# Board_Layout.net
KiCad netlist of a schematic drawn in EAGLE
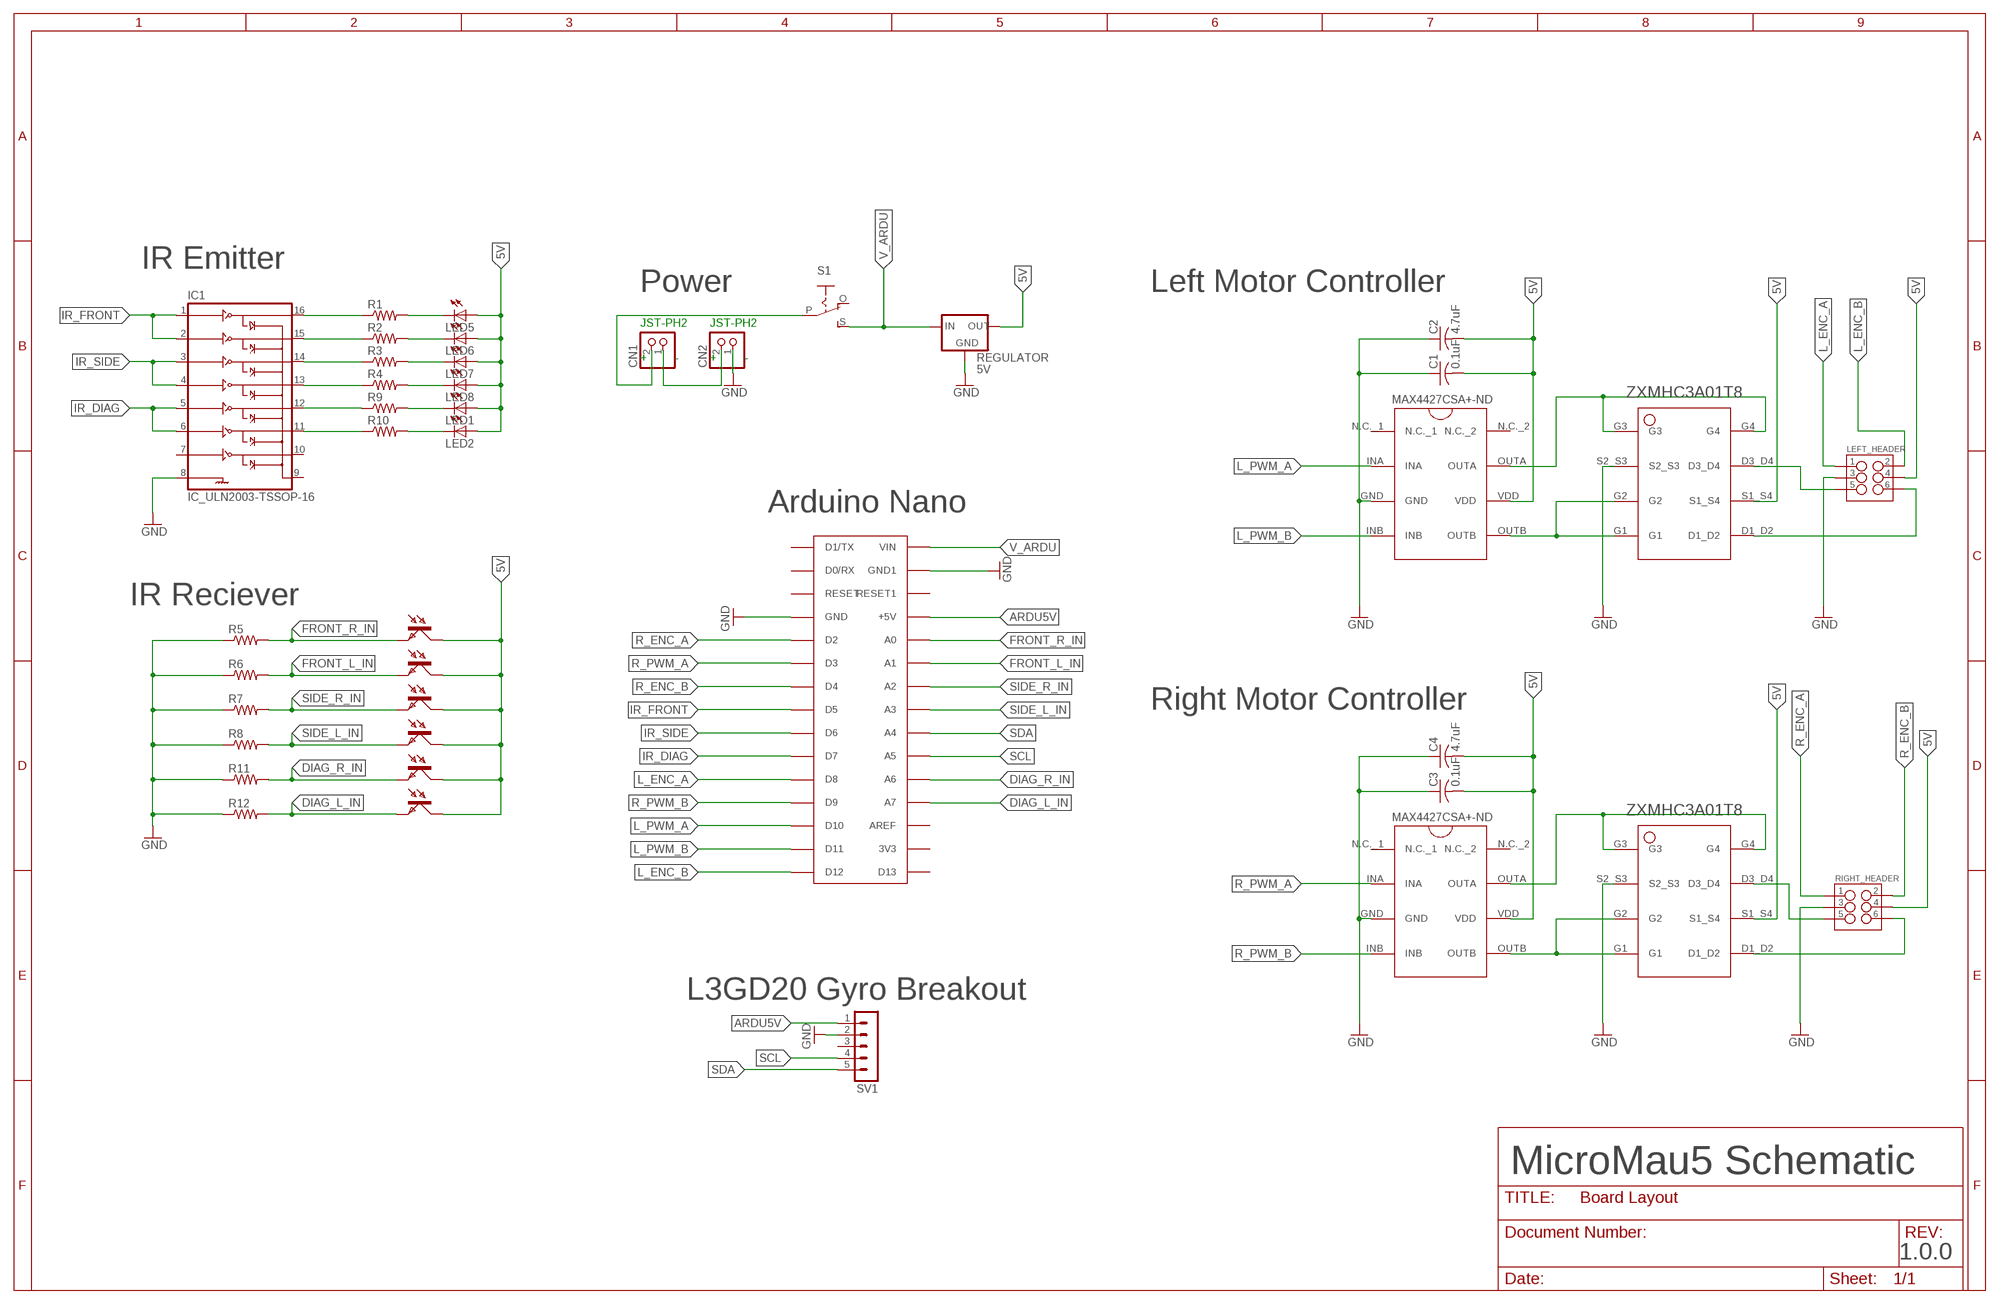
[diagram p0: schematic, sheet 1]

(export (version "E")
  (design (tool "Eeschema 10.0.6"))
  (components
    (comp (ref "C1")
      (value "0.1uF")
      (footprint "eagle-import:C0805")
      (libsource (lib "eagle-import") (part "C-USC0805"))
    )
    (comp (ref "C2")
      (value "4.7uF")
      (footprint "eagle-import:C0805")
      (libsource (lib "eagle-import") (part "C-USC0805"))
    )
    (comp (ref "C3")
      (value "0.1uF")
      (footprint "eagle-import:C0805")
      (libsource (lib "eagle-import") (part "C-USC0805"))
    )
    (comp (ref "C4")
      (value "4.7uF")
      (footprint "eagle-import:C0805")
      (libsource (lib "eagle-import") (part "C-USC0805"))
    )
    (comp (ref "CN1")
      (value "JST_2PIN-THM")
      (footprint "eagle-import:JST-PH-2-THM")
      (libsource (lib "eagle-import") (part "JST_2PIN-THM"))
    )
    (comp (ref "CN2")
      (value "JST_2PIN-THM")
      (footprint "eagle-import:JST-PH-2-THM")
      (libsource (lib "eagle-import") (part "JST_2PIN-THM"))
    )
    (comp (ref "IC1")
      (value "IC_ULN2003-TSSOP-16")
      (footprint "eagle-import:TSSOP-16")
      (libsource (lib "eagle-import") (part "IC_ULN2003-TSSOP-16"))
    )
    (comp (ref "LED1")
      (value "LED5MM")
      (footprint "eagle-import:LED5MM")
      (libsource (lib "eagle-import") (part "LED5MM"))
    )
    (comp (ref "LED2")
      (value "LED5MM")
      (footprint "eagle-import:LED5MM")
      (libsource (lib "eagle-import") (part "LED5MM"))
    )
    (comp (ref "LED5")
      (value "LED5MM")
      (footprint "eagle-import:LED5MM")
      (libsource (lib "eagle-import") (part "LED5MM"))
    )
    (comp (ref "LED6")
      (value "LED5MM")
      (footprint "eagle-import:LED5MM")
      (libsource (lib "eagle-import") (part "LED5MM"))
    )
    (comp (ref "LED7")
      (value "LED5MM")
      (footprint "eagle-import:LED5MM")
      (libsource (lib "eagle-import") (part "LED5MM"))
    )
    (comp (ref "LED8")
      (value "LED5MM")
      (footprint "eagle-import:LED5MM")
      (libsource (lib "eagle-import") (part "LED5MM"))
    )
    (comp (ref "LEFT_HEADER")
      (value "M03X2SHROUD")
      (footprint "eagle-import:2X3-SHROUDED")
      (libsource (lib "eagle-import") (part "M03X2SHROUD"))
    )
    (comp (ref "R1")
      (value "R-US_M0805")
      (footprint "eagle-import:M0805")
      (libsource (lib "eagle-import") (part "R-US_M0805"))
    )
    (comp (ref "R2")
      (value "R-US_M0805")
      (footprint "eagle-import:M0805")
      (libsource (lib "eagle-import") (part "R-US_M0805"))
    )
    (comp (ref "R3")
      (value "R-US_M0805")
      (footprint "eagle-import:M0805")
      (libsource (lib "eagle-import") (part "R-US_M0805"))
    )
    (comp (ref "R4")
      (value "R-US_M0805")
      (footprint "eagle-import:M0805")
      (libsource (lib "eagle-import") (part "R-US_M0805"))
    )
    (comp (ref "R5")
      (value "R-US_R0805")
      (footprint "eagle-import:R0805")
      (libsource (lib "eagle-import") (part "R-US_R0805"))
    )
    (comp (ref "R6")
      (value "R-US_R0805")
      (footprint "eagle-import:R0805")
      (libsource (lib "eagle-import") (part "R-US_R0805"))
    )
    (comp (ref "R7")
      (value "R-US_R0805")
      (footprint "eagle-import:R0805")
      (libsource (lib "eagle-import") (part "R-US_R0805"))
    )
    (comp (ref "R8")
      (value "R-US_R0805")
      (footprint "eagle-import:R0805")
      (libsource (lib "eagle-import") (part "R-US_R0805"))
    )
    (comp (ref "R9")
      (value "R-US_M0805")
      (footprint "eagle-import:M0805")
      (libsource (lib "eagle-import") (part "R-US_M0805"))
    )
    (comp (ref "R10")
      (value "R-US_M0805")
      (footprint "eagle-import:M0805")
      (libsource (lib "eagle-import") (part "R-US_M0805"))
    )
    (comp (ref "R11")
      (value "R-US_R0805")
      (footprint "eagle-import:R0805")
      (libsource (lib "eagle-import") (part "R-US_R0805"))
    )
    (comp (ref "R12")
      (value "R-US_R0805")
      (footprint "eagle-import:R0805")
      (libsource (lib "eagle-import") (part "R-US_R0805"))
    )
    (comp (ref "REGULATOR")
      (value "5V")
      (footprint "eagle-import:TO92-INLINE")
      (libsource (lib "eagle-import") (part "MCP1700INLINE"))
    )
    (comp (ref "RIGHT_HEADER")
      (value "M03X2SHROUD")
      (footprint "eagle-import:2X3-SHROUDED")
      (libsource (lib "eagle-import") (part "M03X2SHROUD"))
    )
    (comp (ref "S1")
      (value "EG1218S")
      (footprint "eagle-import:EG1218")
      (libsource (lib "eagle-import") (part "EG1218S"))
    )
    (comp (ref "SV1")
      (value "MA05-1")
      (footprint "eagle-import:MA05-1")
      (libsource (lib "eagle-import") (part "MA05-1"))
    )
    (comp (ref "T1")
      (value "BPX81")
      (footprint "eagle-import:BPX81")
      (libsource (lib "eagle-import") (part "BPX81"))
    )
    (comp (ref "T2")
      (value "BPX81")
      (footprint "eagle-import:BPX81")
      (libsource (lib "eagle-import") (part "BPX81"))
    )
    (comp (ref "T3")
      (value "BPX81")
      (footprint "eagle-import:BPX81")
      (libsource (lib "eagle-import") (part "BPX81"))
    )
    (comp (ref "T4")
      (value "BPX81")
      (footprint "eagle-import:BPX81")
      (libsource (lib "eagle-import") (part "BPX81"))
    )
    (comp (ref "T5")
      (value "BPX81")
      (footprint "eagle-import:BPX81")
      (libsource (lib "eagle-import") (part "BPX81"))
    )
    (comp (ref "T6")
      (value "BPX81")
      (footprint "eagle-import:BPX81")
      (libsource (lib "eagle-import") (part "BPX81"))
    )
    (comp (ref "U$1")
      (value "MAX4427CSA+-ND")
      (footprint "eagle-import:MAX4427CSA+-ND")
      (libsource (lib "eagle-import") (part "MAX4427CSA+-ND"))
    )
    (comp (ref "U$2")
      (value "ZXMHC3A01T8")
      (footprint "eagle-import:ZXMHC3A01T8")
      (libsource (lib "eagle-import") (part "ZXMHC3A01T8"))
    )
    (comp (ref "U$3")
      (value "ARDUINONANO")
      (footprint "eagle-import:PDIP-32")
      (libsource (lib "eagle-import") (part "ARDUINONANO"))
    )
    (comp (ref "U$4")
      (value "MAX4427CSA+-ND")
      (footprint "eagle-import:MAX4427CSA+-ND")
      (libsource (lib "eagle-import") (part "MAX4427CSA+-ND"))
    )
    (comp (ref "U$5")
      (value "ZXMHC3A01T8")
      (footprint "eagle-import:ZXMHC3A01T8")
      (libsource (lib "eagle-import") (part "ZXMHC3A01T8"))
    )
  )
  (nets
    (net (code "1") (name "5V") (class "Default")
      (node (ref "C1") (pin "2") (pinfunction "2_2") (pintype "passive"))
      (node (ref "C2") (pin "2") (pinfunction "2_2") (pintype "passive"))
      (node (ref "C3") (pin "2") (pinfunction "2_2") (pintype "passive"))
      (node (ref "C4") (pin "2") (pinfunction "2_2") (pintype "passive"))
      (node (ref "LED1") (pin "A") (pinfunction "A_A") (pintype "passive"))
      (node (ref "LED2") (pin "A") (pinfunction "A_A") (pintype "passive"))
      (node (ref "LED5") (pin "A") (pinfunction "A_A") (pintype "passive"))
      (node (ref "LED6") (pin "A") (pinfunction "A_A") (pintype "passive"))
      (node (ref "LED7") (pin "A") (pinfunction "A_A") (pintype "passive"))
      (node (ref "LED8") (pin "A") (pinfunction "A_A") (pintype "passive"))
      (node (ref "LEFT_HEADER") (pin "4") (pinfunction "4_4") (pintype "bidirectional"))
      (node (ref "REGULATOR") (pin "3") (pinfunction "OUT_3") (pintype "passive"))
      (node (ref "RIGHT_HEADER") (pin "4") (pinfunction "4_4") (pintype "bidirectional"))
      (node (ref "T1") (pin "C") (pinfunction "C_C") (pintype "passive"))
      (node (ref "T2") (pin "C") (pinfunction "C_C") (pintype "passive"))
      (node (ref "T3") (pin "C") (pinfunction "C_C") (pintype "passive"))
      (node (ref "T4") (pin "C") (pinfunction "C_C") (pintype "passive"))
      (node (ref "T5") (pin "C") (pinfunction "C_C") (pintype "passive"))
      (node (ref "T6") (pin "C") (pinfunction "C_C") (pintype "passive"))
      (node (ref "U$1") (pin "VDD") (pinfunction "VDD_VDD") (pintype "bidirectional"))
      (node (ref "U$2") (pin "S1_S4") (pinfunction "S1_S4_S1_S4") (pintype "bidirectional"))
      (node (ref "U$4") (pin "VDD") (pinfunction "VDD_VDD") (pintype "bidirectional"))
      (node (ref "U$5") (pin "S1_S4") (pinfunction "S1_S4_S1_S4") (pintype "bidirectional"))
    )
    (net (code "2") (name "ARDU5V") (class "Default")
      (node (ref "SV1") (pin "1") (pinfunction "1_1") (pintype "passive"))
      (node (ref "U$3") (pin "+5V") (pinfunction "+5V_+5V") (pintype "bidirectional"))
    )
    (net (code "3") (name "DIAG_L_IN") (class "Default")
      (node (ref "R12") (pin "2") (pinfunction "2_2") (pintype "passive"))
      (node (ref "T6") (pin "E") (pinfunction "E_E") (pintype "passive"))
      (node (ref "U$3") (pin "A7") (pinfunction "A7_A7") (pintype "bidirectional"))
    )
    (net (code "4") (name "DIAG_R_IN") (class "Default")
      (node (ref "R11") (pin "2") (pinfunction "2_2") (pintype "passive"))
      (node (ref "T5") (pin "E") (pinfunction "E_E") (pintype "passive"))
      (node (ref "U$3") (pin "A6") (pinfunction "A6_A6") (pintype "bidirectional"))
    )
    (net (code "5") (name "FRONT_L_IN") (class "Default")
      (node (ref "R6") (pin "2") (pinfunction "2_2") (pintype "passive"))
      (node (ref "T3") (pin "E") (pinfunction "E_E") (pintype "passive"))
      (node (ref "U$3") (pin "A1") (pinfunction "A1_A1") (pintype "bidirectional"))
    )
    (net (code "6") (name "FRONT_R_IN") (class "Default")
      (node (ref "R5") (pin "2") (pinfunction "2_2") (pintype "passive"))
      (node (ref "T2") (pin "E") (pinfunction "E_E") (pintype "passive"))
      (node (ref "U$3") (pin "A0") (pinfunction "A0_A0") (pintype "bidirectional"))
    )
    (net (code "7") (name "GND") (class "Default")
      (node (ref "C1") (pin "1") (pinfunction "1_1") (pintype "passive"))
      (node (ref "C2") (pin "1") (pinfunction "1_1") (pintype "passive"))
      (node (ref "C3") (pin "1") (pinfunction "1_1") (pintype "passive"))
      (node (ref "C4") (pin "1") (pinfunction "1_1") (pintype "passive"))
      (node (ref "CN2") (pin "1") (pinfunction "2_1") (pintype "passive"))
      (node (ref "IC1") (pin "8") (pinfunction "GND_8") (pintype "bidirectional"))
      (node (ref "LEFT_HEADER") (pin "3") (pinfunction "3_3") (pintype "bidirectional"))
      (node (ref "R11") (pin "1") (pinfunction "1_1") (pintype "passive"))
      (node (ref "R12") (pin "1") (pinfunction "1_1") (pintype "passive"))
      (node (ref "R5") (pin "1") (pinfunction "1_1") (pintype "passive"))
      (node (ref "R6") (pin "1") (pinfunction "1_1") (pintype "passive"))
      (node (ref "R7") (pin "1") (pinfunction "1_1") (pintype "passive"))
      (node (ref "R8") (pin "1") (pinfunction "1_1") (pintype "passive"))
      (node (ref "REGULATOR") (pin "1") (pinfunction "GND_1") (pintype "input"))
      (node (ref "RIGHT_HEADER") (pin "3") (pinfunction "3_3") (pintype "bidirectional"))
      (node (ref "SV1") (pin "2") (pinfunction "2_2") (pintype "passive"))
      (node (ref "U$1") (pin "GND") (pinfunction "GND_GND") (pintype "bidirectional"))
      (node (ref "U$2") (pin "S2_S3") (pinfunction "S2_S3_S2_S3") (pintype "bidirectional"))
      (node (ref "U$3") (pin "GND") (pinfunction "GND_GND") (pintype "bidirectional"))
      (node (ref "U$3") (pin "GND1") (pinfunction "GND1_GND1") (pintype "bidirectional"))
      (node (ref "U$4") (pin "GND") (pinfunction "GND_GND") (pintype "bidirectional"))
      (node (ref "U$5") (pin "S2_S3") (pinfunction "S2_S3_S2_S3") (pintype "bidirectional"))
    )
    (net (code "8") (name "IR_DIAG") (class "Default")
      (node (ref "IC1") (pin "5") (pinfunction "5B_5") (pintype "bidirectional"))
      (node (ref "IC1") (pin "6") (pinfunction "6B_6") (pintype "bidirectional"))
      (node (ref "U$3") (pin "D7") (pinfunction "D7_D7") (pintype "bidirectional"))
    )
    (net (code "9") (name "IR_FRONT") (class "Default")
      (node (ref "IC1") (pin "1") (pinfunction "1B_1") (pintype "bidirectional"))
      (node (ref "IC1") (pin "2") (pinfunction "2B_2") (pintype "bidirectional"))
      (node (ref "U$3") (pin "D5") (pinfunction "D5_D5") (pintype "bidirectional"))
    )
    (net (code "10") (name "IR_SIDE") (class "Default")
      (node (ref "IC1") (pin "3") (pinfunction "3B_3") (pintype "bidirectional"))
      (node (ref "IC1") (pin "4") (pinfunction "4B_4") (pintype "bidirectional"))
      (node (ref "U$3") (pin "D6") (pinfunction "D6_D6") (pintype "bidirectional"))
    )
    (net (code "11") (name "L_ENC_A") (class "Default")
      (node (ref "LEFT_HEADER") (pin "1") (pinfunction "1_1") (pintype "bidirectional"))
      (node (ref "U$3") (pin "D8") (pinfunction "D8_D8") (pintype "bidirectional"))
    )
    (net (code "12") (name "L_ENC_B") (class "Default")
      (node (ref "LEFT_HEADER") (pin "2") (pinfunction "2_2") (pintype "bidirectional"))
      (node (ref "U$3") (pin "D12") (pinfunction "D12_D12") (pintype "bidirectional"))
    )
    (net (code "13") (name "L_PWM_A") (class "Default")
      (node (ref "U$1") (pin "INA") (pinfunction "INA_INA") (pintype "bidirectional"))
      (node (ref "U$3") (pin "D10") (pinfunction "D10_D10") (pintype "bidirectional"))
    )
    (net (code "14") (name "L_PWM_B") (class "Default")
      (node (ref "U$1") (pin "INB") (pinfunction "INB_INB") (pintype "bidirectional"))
      (node (ref "U$3") (pin "D11") (pinfunction "D11_D11") (pintype "bidirectional"))
    )
    (net (code "15") (name "Net-(CN1-1)") (class "Default")
      (node (ref "CN1") (pin "2") (pinfunction "1_2") (pintype "passive"))
      (node (ref "S1") (pin "P") (pinfunction "P_P") (pintype "passive"))
    )
    (net (code "16") (name "Net-(CN1-2)") (class "Default")
      (node (ref "CN1") (pin "1") (pinfunction "2_1") (pintype "passive"))
      (node (ref "CN2") (pin "2") (pinfunction "1_2") (pintype "passive"))
    )
    (net (code "17") (name "Net-(IC1-1C)") (class "Default")
      (node (ref "IC1") (pin "16") (pinfunction "1C_16") (pintype "bidirectional"))
      (node (ref "R1") (pin "1") (pinfunction "1_1") (pintype "passive"))
    )
    (net (code "18") (name "Net-(IC1-2C)") (class "Default")
      (node (ref "IC1") (pin "15") (pinfunction "2C_15") (pintype "bidirectional"))
      (node (ref "R2") (pin "1") (pinfunction "1_1") (pintype "passive"))
    )
    (net (code "19") (name "Net-(IC1-3C)") (class "Default")
      (node (ref "IC1") (pin "14") (pinfunction "3C_14") (pintype "bidirectional"))
      (node (ref "R3") (pin "1") (pinfunction "1_1") (pintype "passive"))
    )
    (net (code "20") (name "Net-(IC1-4C)") (class "Default")
      (node (ref "IC1") (pin "13") (pinfunction "4C_13") (pintype "bidirectional"))
      (node (ref "R4") (pin "1") (pinfunction "1_1") (pintype "passive"))
    )
    (net (code "21") (name "Net-(IC1-5C)") (class "Default")
      (node (ref "IC1") (pin "12") (pinfunction "5C_12") (pintype "bidirectional"))
      (node (ref "R9") (pin "1") (pinfunction "1_1") (pintype "passive"))
    )
    (net (code "22") (name "Net-(IC1-6C)") (class "Default")
      (node (ref "IC1") (pin "11") (pinfunction "6C_11") (pintype "bidirectional"))
      (node (ref "R10") (pin "1") (pinfunction "1_1") (pintype "passive"))
    )
    (net (code "23") (name "Net-(LED1-C)") (class "Default")
      (node (ref "LED1") (pin "K") (pinfunction "C_K") (pintype "passive"))
      (node (ref "R9") (pin "2") (pinfunction "2_2") (pintype "passive"))
    )
    (net (code "24") (name "Net-(LED2-C)") (class "Default")
      (node (ref "LED2") (pin "K") (pinfunction "C_K") (pintype "passive"))
      (node (ref "R10") (pin "2") (pinfunction "2_2") (pintype "passive"))
    )
    (net (code "25") (name "Net-(LED5-C)") (class "Default")
      (node (ref "LED5") (pin "K") (pinfunction "C_K") (pintype "passive"))
      (node (ref "R1") (pin "2") (pinfunction "2_2") (pintype "passive"))
    )
    (net (code "26") (name "Net-(LED6-C)") (class "Default")
      (node (ref "LED6") (pin "K") (pinfunction "C_K") (pintype "passive"))
      (node (ref "R2") (pin "2") (pinfunction "2_2") (pintype "passive"))
    )
    (net (code "27") (name "Net-(LED7-C)") (class "Default")
      (node (ref "LED7") (pin "K") (pinfunction "C_K") (pintype "passive"))
      (node (ref "R3") (pin "2") (pinfunction "2_2") (pintype "passive"))
    )
    (net (code "28") (name "Net-(LED8-C)") (class "Default")
      (node (ref "LED8") (pin "K") (pinfunction "C_K") (pintype "passive"))
      (node (ref "R4") (pin "2") (pinfunction "2_2") (pintype "passive"))
    )
    (net (code "29") (name "Net-(LEFT_HEADER-Pad5)") (class "Default")
      (node (ref "LEFT_HEADER") (pin "5") (pinfunction "5_5") (pintype "bidirectional"))
      (node (ref "U$2") (pin "D3_D4") (pinfunction "D3_D4_D3_D4") (pintype "bidirectional"))
    )
    (net (code "30") (name "Net-(LEFT_HEADER-Pad6)") (class "Default")
      (node (ref "LEFT_HEADER") (pin "6") (pinfunction "6_6") (pintype "bidirectional"))
      (node (ref "U$2") (pin "D1_D2") (pinfunction "D1_D2_D1_D2") (pintype "bidirectional"))
    )
    (net (code "31") (name "Net-(RIGHT_HEADER-Pad5)") (class "Default")
      (node (ref "RIGHT_HEADER") (pin "5") (pinfunction "5_5") (pintype "bidirectional"))
      (node (ref "U$5") (pin "D3_D4") (pinfunction "D3_D4_D3_D4") (pintype "bidirectional"))
    )
    (net (code "32") (name "Net-(RIGHT_HEADER-Pad6)") (class "Default")
      (node (ref "RIGHT_HEADER") (pin "6") (pinfunction "6_6") (pintype "bidirectional"))
      (node (ref "U$5") (pin "D1_D2") (pinfunction "D1_D2_D1_D2") (pintype "bidirectional"))
    )
    (net (code "33") (name "Net-(U$1-PadOUTA)") (class "Default")
      (node (ref "U$1") (pin "OUTA") (pinfunction "OUTA_OUTA") (pintype "bidirectional"))
      (node (ref "U$2") (pin "G3") (pinfunction "G3_G3") (pintype "bidirectional"))
      (node (ref "U$2") (pin "G4") (pinfunction "G4_G4") (pintype "bidirectional"))
    )
    (net (code "34") (name "Net-(U$1-PadOUTB)") (class "Default")
      (node (ref "U$1") (pin "OUTB") (pinfunction "OUTB_OUTB") (pintype "bidirectional"))
      (node (ref "U$2") (pin "G1") (pinfunction "G1_G1") (pintype "bidirectional"))
      (node (ref "U$2") (pin "G2") (pinfunction "G2_G2") (pintype "bidirectional"))
    )
    (net (code "35") (name "Net-(U$4-PadOUTA)") (class "Default")
      (node (ref "U$4") (pin "OUTA") (pinfunction "OUTA_OUTA") (pintype "bidirectional"))
      (node (ref "U$5") (pin "G3") (pinfunction "G3_G3") (pintype "bidirectional"))
      (node (ref "U$5") (pin "G4") (pinfunction "G4_G4") (pintype "bidirectional"))
    )
    (net (code "36") (name "Net-(U$4-PadOUTB)") (class "Default")
      (node (ref "U$4") (pin "OUTB") (pinfunction "OUTB_OUTB") (pintype "bidirectional"))
      (node (ref "U$5") (pin "G1") (pinfunction "G1_G1") (pintype "bidirectional"))
      (node (ref "U$5") (pin "G2") (pinfunction "G2_G2") (pintype "bidirectional"))
    )
    (net (code "37") (name "R_ENC_A") (class "Default")
      (node (ref "RIGHT_HEADER") (pin "1") (pinfunction "1_1") (pintype "bidirectional"))
      (node (ref "U$3") (pin "D2") (pinfunction "D2_D2") (pintype "bidirectional"))
    )
    (net (code "38") (name "R_ENC_B") (class "Default")
      (node (ref "RIGHT_HEADER") (pin "2") (pinfunction "2_2") (pintype "bidirectional"))
      (node (ref "U$3") (pin "D4") (pinfunction "D4_D4") (pintype "bidirectional"))
    )
    (net (code "39") (name "R_PWM_A") (class "Default")
      (node (ref "U$3") (pin "D3") (pinfunction "D3_D3") (pintype "bidirectional"))
      (node (ref "U$4") (pin "INA") (pinfunction "INA_INA") (pintype "bidirectional"))
    )
    (net (code "40") (name "R_PWM_B") (class "Default")
      (node (ref "U$3") (pin "D9") (pinfunction "D9_D9") (pintype "bidirectional"))
      (node (ref "U$4") (pin "INB") (pinfunction "INB_INB") (pintype "bidirectional"))
    )
    (net (code "41") (name "SCL") (class "Default")
      (node (ref "SV1") (pin "4") (pinfunction "4_4") (pintype "passive"))
      (node (ref "U$3") (pin "A5") (pinfunction "A5_A5") (pintype "bidirectional"))
    )
    (net (code "42") (name "SDA") (class "Default")
      (node (ref "SV1") (pin "5") (pinfunction "5_5") (pintype "passive"))
      (node (ref "U$3") (pin "A4") (pinfunction "A4_A4") (pintype "bidirectional"))
    )
    (net (code "43") (name "SIDE_L_IN") (class "Default")
      (node (ref "R8") (pin "2") (pinfunction "2_2") (pintype "passive"))
      (node (ref "T4") (pin "E") (pinfunction "E_E") (pintype "passive"))
      (node (ref "U$3") (pin "A3") (pinfunction "A3_A3") (pintype "bidirectional"))
    )
    (net (code "44") (name "SIDE_R_IN") (class "Default")
      (node (ref "R7") (pin "2") (pinfunction "2_2") (pintype "passive"))
      (node (ref "T1") (pin "E") (pinfunction "E_E") (pintype "passive"))
      (node (ref "U$3") (pin "A2") (pinfunction "A2_A2") (pintype "bidirectional"))
    )
    (net (code "45") (name "V_ARDU") (class "Default")
      (node (ref "REGULATOR") (pin "2") (pinfunction "IN_2") (pintype "input"))
      (node (ref "S1") (pin "S") (pinfunction "S_S") (pintype "passive"))
      (node (ref "U$3") (pin "VIN") (pinfunction "VIN_VIN") (pintype "bidirectional"))
    )
    (net (code "46") (name "unconnected-(IC1-7B-Pad7)") (class "Default")
      (node (ref "IC1") (pin "7") (pinfunction "7B_7") (pintype "bidirectional"))
    )
    (net (code "47") (name "unconnected-(IC1-7C-Pad10)") (class "Default")
      (node (ref "IC1") (pin "10") (pinfunction "7C_10") (pintype "bidirectional"))
    )
    (net (code "48") (name "unconnected-(IC1-COM-Pad9)") (class "Default")
      (node (ref "IC1") (pin "9") (pinfunction "COM_9") (pintype "bidirectional"))
    )
    (net (code "49") (name "unconnected-(S1-PadO)") (class "Default")
      (node (ref "S1") (pin "O") (pinfunction "O_O") (pintype "passive"))
    )
    (net (code "50") (name "unconnected-(SV1-Pad3)") (class "Default")
      (node (ref "SV1") (pin "3") (pinfunction "3_3") (pintype "passive"))
    )
    (net (code "51") (name "unconnected-(U$1-PadN.C._1)") (class "Default")
      (node (ref "U$1") (pin "N.C._1") (pinfunction "N.C._1_N.C._1") (pintype "bidirectional"))
    )
    (net (code "52") (name "unconnected-(U$1-PadN.C._2)") (class "Default")
      (node (ref "U$1") (pin "N.C._2") (pinfunction "N.C._2_N.C._2") (pintype "bidirectional"))
    )
    (net (code "53") (name "unconnected-(U$3-Pad3V3)") (class "Default")
      (node (ref "U$3") (pin "3V3") (pinfunction "3V3_3V3") (pintype "bidirectional"))
    )
    (net (code "54") (name "unconnected-(U$3-PadAREF)") (class "Default")
      (node (ref "U$3") (pin "AREF") (pinfunction "AREF_AREF") (pintype "bidirectional"))
    )
    (net (code "55") (name "unconnected-(U$3-PadD0{slash}RX)") (class "Default")
      (node (ref "U$3") (pin "D0/RX") (pinfunction "D0/RX_D0/RX") (pintype "bidirectional"))
    )
    (net (code "56") (name "unconnected-(U$3-PadD1{slash}TX)") (class "Default")
      (node (ref "U$3") (pin "D1/TX") (pinfunction "D1/TX_D1/TX") (pintype "bidirectional"))
    )
    (net (code "57") (name "unconnected-(U$3-PadD13)") (class "Default")
      (node (ref "U$3") (pin "D13") (pinfunction "D13_D13") (pintype "bidirectional"))
    )
    (net (code "58") (name "unconnected-(U$3-PadRESET)") (class "Default")
      (node (ref "U$3") (pin "RESET") (pinfunction "RESET_RESET") (pintype "bidirectional"))
    )
    (net (code "59") (name "unconnected-(U$3-PadRESET1)") (class "Default")
      (node (ref "U$3") (pin "RESET1") (pinfunction "RESET1_RESET1") (pintype "bidirectional"))
    )
    (net (code "60") (name "unconnected-(U$4-PadN.C._1)") (class "Default")
      (node (ref "U$4") (pin "N.C._1") (pinfunction "N.C._1_N.C._1") (pintype "bidirectional"))
    )
    (net (code "61") (name "unconnected-(U$4-PadN.C._2)") (class "Default")
      (node (ref "U$4") (pin "N.C._2") (pinfunction "N.C._2_N.C._2") (pintype "bidirectional"))
    )
  )
)
